# External_Camera_HAT_LvlShifters.net
KiCad netlist of a schematic drawn in Altium Designer
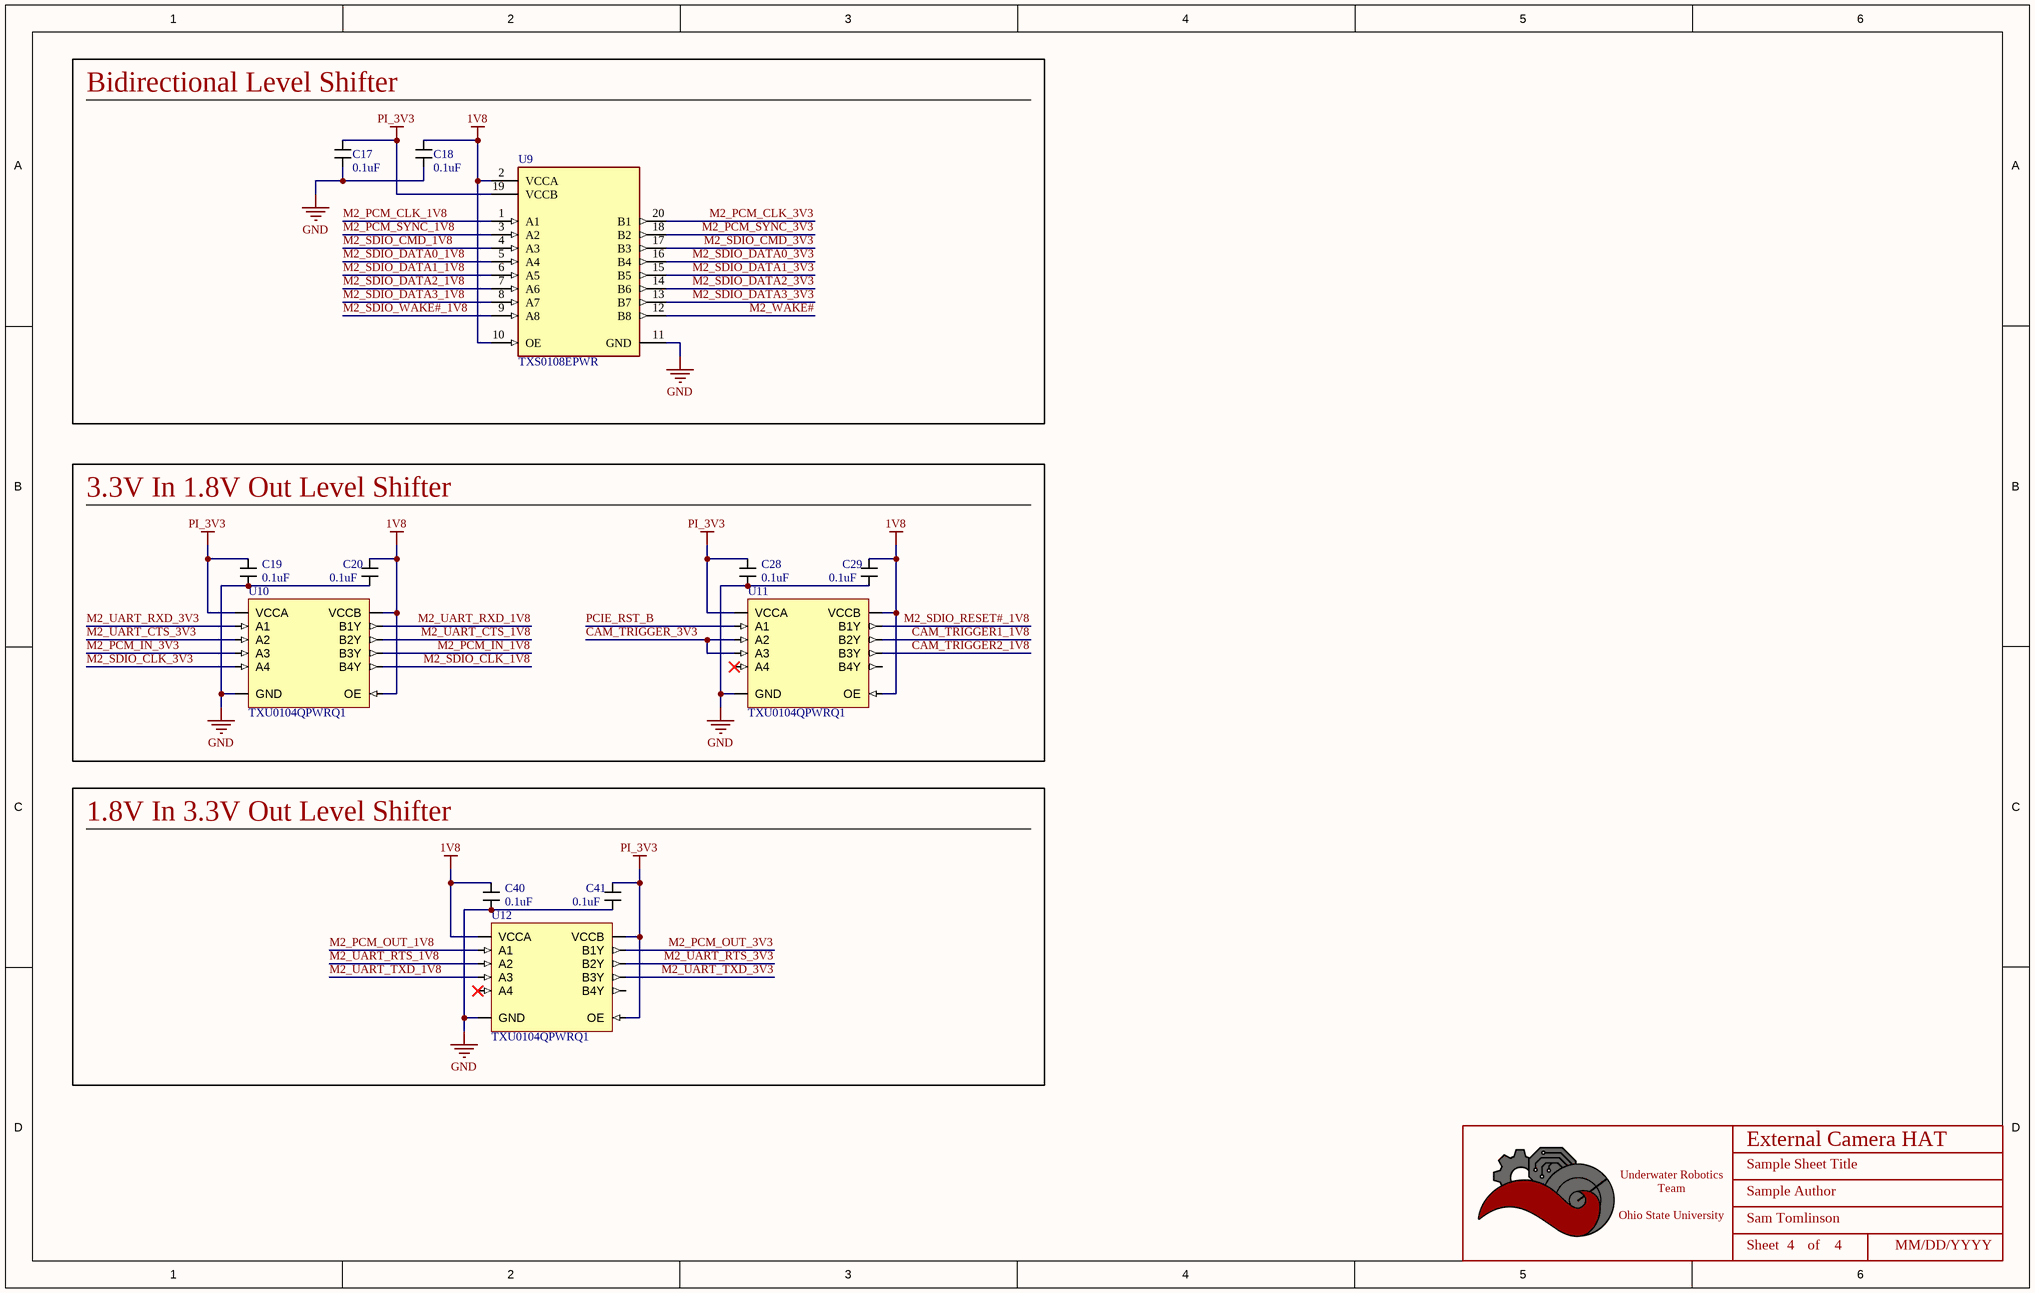
[diagram p0: External_Camera_HAT_LvlShifters.SchDoc]

(export (version "E")
  (design (tool "Eeschema 10.0.6"))
  (components
    (comp (ref "C17")
      (value "0.1uF")
      (footprint "CAPACITOR_0402")
      (description "Cap 100nF 25V +/-10%\r\nCeramic 0402")
      (fields
        (field (name "TOLERANCE") "+/- 10%")
        (field (name "VOLTAGE") "25V")
        (field (name "MADE BY") "Robert Pafford")
      )
      (libsource (lib "Capacitors") (part "CAPACITOR_0.1uF_0402"))
    )
    (comp (ref "C18")
      (value "0.1uF")
      (footprint "CAPACITOR_0402")
      (description "Cap 100nF 25V +/-10%\r\nCeramic 0402")
      (fields
        (field (name "TOLERANCE") "+/- 10%")
        (field (name "VOLTAGE") "25V")
        (field (name "MADE BY") "Robert Pafford")
      )
      (libsource (lib "Capacitors") (part "CAPACITOR_0.1uF_0402"))
    )
    (comp (ref "C19")
      (value "0.1uF")
      (footprint "CAPACITOR_0402")
      (description "Cap 100nF 25V +/-10%\r\nCeramic 0402")
      (fields
        (field (name "TOLERANCE") "+/- 10%")
        (field (name "VOLTAGE") "25V")
        (field (name "MADE BY") "Robert Pafford")
      )
      (libsource (lib "Capacitors") (part "CAPACITOR_0.1uF_0402"))
    )
    (comp (ref "C20")
      (value "0.1uF")
      (footprint "CAPACITOR_0402")
      (description "Cap 100nF 25V +/-10%\r\nCeramic 0402")
      (fields
        (field (name "TOLERANCE") "+/- 10%")
        (field (name "VOLTAGE") "25V")
        (field (name "MADE BY") "Robert Pafford")
      )
      (libsource (lib "Capacitors") (part "CAPACITOR_0.1uF_0402"))
    )
    (comp (ref "C28")
      (value "0.1uF")
      (footprint "CAPACITOR_0402")
      (description "Cap 100nF 25V +/-10%\r\nCeramic 0402")
      (fields
        (field (name "TOLERANCE") "+/- 10%")
        (field (name "VOLTAGE") "25V")
        (field (name "MADE BY") "Robert Pafford")
      )
      (libsource (lib "Capacitors") (part "CAPACITOR_0.1uF_0402"))
    )
    (comp (ref "C29")
      (value "0.1uF")
      (footprint "CAPACITOR_0402")
      (description "Cap 100nF 25V +/-10%\r\nCeramic 0402")
      (fields
        (field (name "TOLERANCE") "+/- 10%")
        (field (name "VOLTAGE") "25V")
        (field (name "MADE BY") "Robert Pafford")
      )
      (libsource (lib "Capacitors") (part "CAPACITOR_0.1uF_0402"))
    )
    (comp (ref "C40")
      (value "0.1uF")
      (footprint "CAPACITOR_0402")
      (description "Cap 100nF 25V +/-10%\r\nCeramic 0402")
      (fields
        (field (name "TOLERANCE") "+/- 10%")
        (field (name "VOLTAGE") "25V")
        (field (name "MADE BY") "Robert Pafford")
      )
      (libsource (lib "Capacitors") (part "CAPACITOR_0.1uF_0402"))
    )
    (comp (ref "C41")
      (value "0.1uF")
      (footprint "CAPACITOR_0402")
      (description "Cap 100nF 25V +/-10%\r\nCeramic 0402")
      (fields
        (field (name "TOLERANCE") "+/- 10%")
        (field (name "VOLTAGE") "25V")
        (field (name "MADE BY") "Robert Pafford")
      )
      (libsource (lib "Capacitors") (part "CAPACITOR_0.1uF_0402"))
    )
    (comp (ref "U9")
      (value "TXS0108EPWR")
      (footprint "FP-PW0020A-IPC_C")
      (description "IC TRNSLTR BIDIRECTIONAL 20TSSOP")
      (libsource (lib "Altium Content Vault") (part "86128ddf5852d4e934b2dd0188c13f1"))
    )
    (comp (ref "U10")
      (value "TXU0104QPWRQ1")
      (footprint "PW (R-PDSO-G14)")
      (description "Voltage Level Translator Unidirectional 1 Circuit 4 Channel 200Mbps 14-TSSOP")
      (fields (field (name "MADE BY") "Robert Pafford"))
      (libsource (lib "Integrated Circuits") (part "TXU0104QPWRQ1"))
    )
    (comp (ref "U11")
      (value "TXU0104QPWRQ1")
      (footprint "PW (R-PDSO-G14)")
      (description "Voltage Level Translator Unidirectional 1 Circuit 4 Channel 200Mbps 14-TSSOP")
      (fields (field (name "MADE BY") "Robert Pafford"))
      (libsource (lib "Integrated Circuits") (part "TXU0104QPWRQ1"))
    )
    (comp (ref "U12")
      (value "TXU0104QPWRQ1")
      (footprint "PW (R-PDSO-G14)")
      (description "Voltage Level Translator Unidirectional 1 Circuit 4 Channel 200Mbps 14-TSSOP")
      (fields (field (name "MADE BY") "Robert Pafford"))
      (libsource (lib "Integrated Circuits") (part "TXU0104QPWRQ1"))
    )
  )
  (nets
    (net (code "1") (name "/CAM_TRIGGER1_1V8") (class "Default")
      (node (ref "U11") (pin "12") (pinfunction "B2Y_12") (pintype "output"))
    )
    (net (code "2") (name "/CAM_TRIGGER2_1V8") (class "Default")
      (node (ref "U11") (pin "11") (pinfunction "B3Y_11") (pintype "output"))
    )
    (net (code "3") (name "/CAM_TRIGGER_3V3") (class "Default")
      (node (ref "U11") (pin "3") (pinfunction "A2_3") (pintype "input"))
      (node (ref "U11") (pin "4") (pinfunction "A3_4") (pintype "input"))
    )
    (net (code "4") (name "/M2_PCM_CLK_1V8") (class "Default")
      (node (ref "U9") (pin "1") (pinfunction "A1_1") (pintype "input"))
    )
    (net (code "5") (name "/M2_PCM_CLK_3V3") (class "Default")
      (node (ref "U9") (pin "20") (pinfunction "B1_20") (pintype "output"))
    )
    (net (code "6") (name "/M2_PCM_IN_1V8") (class "Default")
      (node (ref "U10") (pin "11") (pinfunction "B3Y_11") (pintype "output"))
    )
    (net (code "7") (name "/M2_PCM_IN_3V3") (class "Default")
      (node (ref "U10") (pin "4") (pinfunction "A3_4") (pintype "input"))
    )
    (net (code "8") (name "/M2_PCM_OUT_1V8") (class "Default")
      (node (ref "U12") (pin "2") (pinfunction "A1_2") (pintype "input"))
    )
    (net (code "9") (name "/M2_PCM_OUT_3V3") (class "Default")
      (node (ref "U12") (pin "13") (pinfunction "B1Y_13") (pintype "output"))
    )
    (net (code "10") (name "/M2_PCM_SYNC_1V8") (class "Default")
      (node (ref "U9") (pin "3") (pinfunction "A2_3") (pintype "input"))
    )
    (net (code "11") (name "/M2_PCM_SYNC_3V3") (class "Default")
      (node (ref "U9") (pin "18") (pinfunction "B2_18") (pintype "output"))
    )
    (net (code "12") (name "/M2_SDIO_CLK_1V8") (class "Default")
      (node (ref "U10") (pin "10") (pinfunction "B4Y_10") (pintype "output"))
    )
    (net (code "13") (name "/M2_SDIO_CLK_3V3") (class "Default")
      (node (ref "U10") (pin "5") (pinfunction "A4_5") (pintype "input"))
    )
    (net (code "14") (name "/M2_SDIO_CMD_1V8") (class "Default")
      (node (ref "U9") (pin "4") (pinfunction "A3_4") (pintype "input"))
    )
    (net (code "15") (name "/M2_SDIO_CMD_3V3") (class "Default")
      (node (ref "U9") (pin "17") (pinfunction "B3_17") (pintype "output"))
    )
    (net (code "16") (name "/M2_SDIO_DATA0_1V8") (class "Default")
      (node (ref "U9") (pin "5") (pinfunction "A4_5") (pintype "input"))
    )
    (net (code "17") (name "/M2_SDIO_DATA0_3V3") (class "Default")
      (node (ref "U9") (pin "16") (pinfunction "B4_16") (pintype "output"))
    )
    (net (code "18") (name "/M2_SDIO_DATA1_1V8") (class "Default")
      (node (ref "U9") (pin "6") (pinfunction "A5_6") (pintype "input"))
    )
    (net (code "19") (name "/M2_SDIO_DATA1_3V3") (class "Default")
      (node (ref "U9") (pin "15") (pinfunction "B5_15") (pintype "output"))
    )
    (net (code "20") (name "/M2_SDIO_DATA2_1V8") (class "Default")
      (node (ref "U9") (pin "7") (pinfunction "A6_7") (pintype "input"))
    )
    (net (code "21") (name "/M2_SDIO_DATA2_3V3") (class "Default")
      (node (ref "U9") (pin "14") (pinfunction "B6_14") (pintype "output"))
    )
    (net (code "22") (name "/M2_SDIO_DATA3_1V8") (class "Default")
      (node (ref "U9") (pin "8") (pinfunction "A7_8") (pintype "input"))
    )
    (net (code "23") (name "/M2_SDIO_DATA3_3V3") (class "Default")
      (node (ref "U9") (pin "13") (pinfunction "B7_13") (pintype "output"))
    )
    (net (code "24") (name "/M2_SDIO_RESET#_1V8") (class "Default")
      (node (ref "U11") (pin "13") (pinfunction "B1Y_13") (pintype "output"))
    )
    (net (code "25") (name "/M2_SDIO_WAKE#_1V8") (class "Default")
      (node (ref "U9") (pin "9") (pinfunction "A8_9") (pintype "input"))
    )
    (net (code "26") (name "/M2_UART_CTS_1V8") (class "Default")
      (node (ref "U10") (pin "12") (pinfunction "B2Y_12") (pintype "output"))
    )
    (net (code "27") (name "/M2_UART_CTS_3V3") (class "Default")
      (node (ref "U10") (pin "3") (pinfunction "A2_3") (pintype "input"))
    )
    (net (code "28") (name "/M2_UART_RTS_1V8") (class "Default")
      (node (ref "U12") (pin "3") (pinfunction "A2_3") (pintype "input"))
    )
    (net (code "29") (name "/M2_UART_RTS_3V3") (class "Default")
      (node (ref "U12") (pin "12") (pinfunction "B2Y_12") (pintype "output"))
    )
    (net (code "30") (name "/M2_UART_RXD_1V8") (class "Default")
      (node (ref "U10") (pin "13") (pinfunction "B1Y_13") (pintype "output"))
    )
    (net (code "31") (name "/M2_UART_RXD_3V3") (class "Default")
      (node (ref "U10") (pin "2") (pinfunction "A1_2") (pintype "input"))
    )
    (net (code "32") (name "/M2_UART_TXD_1V8") (class "Default")
      (node (ref "U12") (pin "4") (pinfunction "A3_4") (pintype "input"))
    )
    (net (code "33") (name "/M2_UART_TXD_3V3") (class "Default")
      (node (ref "U12") (pin "11") (pinfunction "B3Y_11") (pintype "output"))
    )
    (net (code "34") (name "/M2_WAKE#") (class "Default")
      (node (ref "U9") (pin "12") (pinfunction "B8_12") (pintype "output"))
    )
    (net (code "35") (name "/PCIE_RST_B") (class "Default")
      (node (ref "U11") (pin "2") (pinfunction "A1_2") (pintype "input"))
    )
    (net (code "36") (name "1V8") (class "Default")
      (node (ref "C18") (pin "1") (pinfunction "1_1") (pintype "passive"))
      (node (ref "C20") (pin "1") (pinfunction "1_1") (pintype "passive"))
      (node (ref "C29") (pin "1") (pinfunction "1_1") (pintype "passive"))
      (node (ref "C40") (pin "1") (pinfunction "1_1") (pintype "passive"))
      (node (ref "U10") (pin "14") (pinfunction "VCCB_14") (pintype "power_in"))
      (node (ref "U10") (pin "8") (pinfunction "OE_8") (pintype "input"))
      (node (ref "U11") (pin "14") (pinfunction "VCCB_14") (pintype "power_in"))
      (node (ref "U11") (pin "8") (pinfunction "OE_8") (pintype "input"))
      (node (ref "U12") (pin "1") (pinfunction "VCCA_1") (pintype "power_in"))
      (node (ref "U9") (pin "10") (pinfunction "OE_10") (pintype "input"))
      (node (ref "U9") (pin "2") (pinfunction "VCCA_2") (pintype "power_in"))
    )
    (net (code "37") (name "GND") (class "Default")
      (node (ref "C17") (pin "2") (pinfunction "2_2") (pintype "passive"))
      (node (ref "C18") (pin "2") (pinfunction "2_2") (pintype "passive"))
      (node (ref "C19") (pin "2") (pinfunction "2_2") (pintype "passive"))
      (node (ref "C20") (pin "2") (pinfunction "2_2") (pintype "passive"))
      (node (ref "C28") (pin "2") (pinfunction "2_2") (pintype "passive"))
      (node (ref "C29") (pin "2") (pinfunction "2_2") (pintype "passive"))
      (node (ref "C40") (pin "2") (pinfunction "2_2") (pintype "passive"))
      (node (ref "C41") (pin "2") (pinfunction "2_2") (pintype "passive"))
      (node (ref "U10") (pin "7") (pinfunction "GND_7") (pintype "power_in"))
      (node (ref "U11") (pin "7") (pinfunction "GND_7") (pintype "power_in"))
      (node (ref "U12") (pin "7") (pinfunction "GND_7") (pintype "power_in"))
      (node (ref "U9") (pin "11") (pinfunction "GND_11") (pintype "power_in"))
    )
    (net (code "38") (name "PI_3V3") (class "Default")
      (node (ref "C17") (pin "1") (pinfunction "1_1") (pintype "passive"))
      (node (ref "C19") (pin "1") (pinfunction "1_1") (pintype "passive"))
      (node (ref "C28") (pin "1") (pinfunction "1_1") (pintype "passive"))
      (node (ref "C41") (pin "1") (pinfunction "1_1") (pintype "passive"))
      (node (ref "U10") (pin "1") (pinfunction "VCCA_1") (pintype "power_in"))
      (node (ref "U11") (pin "1") (pinfunction "VCCA_1") (pintype "power_in"))
      (node (ref "U12") (pin "14") (pinfunction "VCCB_14") (pintype "power_in"))
      (node (ref "U12") (pin "8") (pinfunction "OE_8") (pintype "input"))
      (node (ref "U9") (pin "19") (pinfunction "VCCB_19") (pintype "power_in"))
    )
    (net (code "39") (name "unconnected-(U11-A4-Pad5)") (class "Default")
      (node (ref "U11") (pin "5") (pinfunction "A4_5") (pintype "input+no_connect"))
    )
    (net (code "40") (name "unconnected-(U11-B4Y-Pad10)") (class "Default")
      (node (ref "U11") (pin "10") (pinfunction "B4Y_10") (pintype "output"))
    )
    (net (code "41") (name "unconnected-(U12-A4-Pad5)") (class "Default")
      (node (ref "U12") (pin "5") (pinfunction "A4_5") (pintype "input+no_connect"))
    )
    (net (code "42") (name "unconnected-(U12-B4Y-Pad10)") (class "Default")
      (node (ref "U12") (pin "10") (pinfunction "B4Y_10") (pintype "output"))
    )
  )
)
